# main.net
KiCad netlist of a schematic drawn in Altium Designer
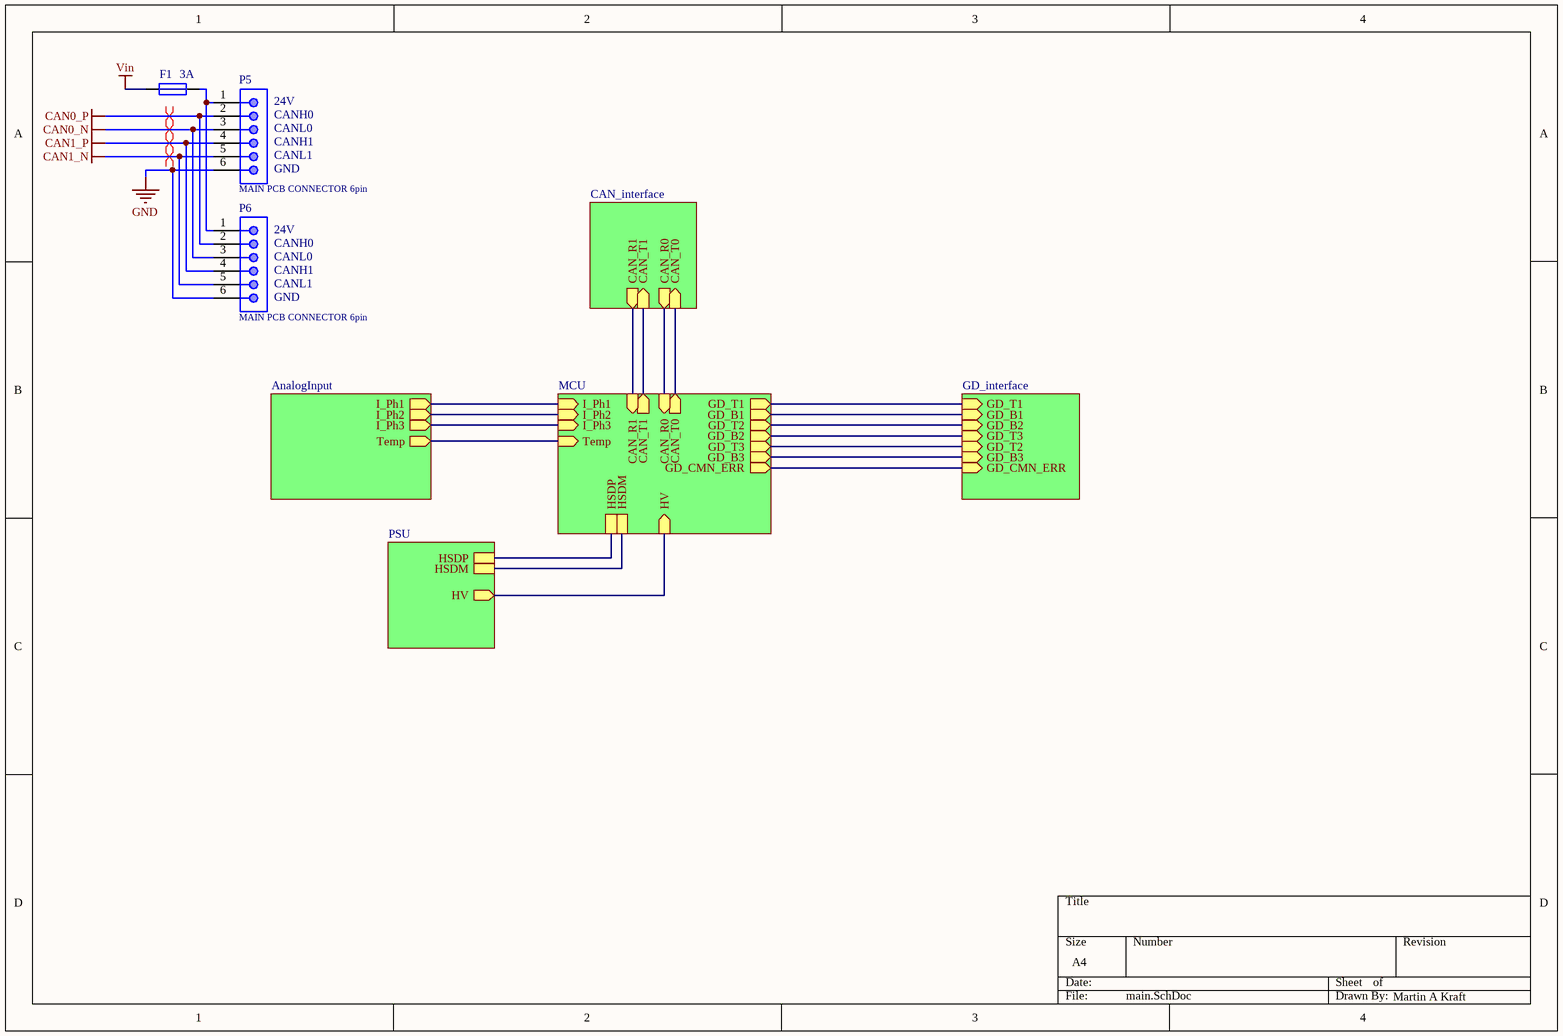
[diagram p0: main.SchDoc]

(export (version "E")
  (design (tool "Eeschema 10.0.6"))
  (components
    (comp (ref "F1")
      (value "3A")
      (footprint "F_OMH125")
      (description "Fuse - universal")
      (libsource (lib "M_Standard") (part "F_Fuse"))
    )
    (comp (ref "P5")
      (value "MAIN PCB CONNECTOR 6pin")
      (footprint "662106145021")
      (description "SMT Male Header WR-MPC3, with SMT Solder Tabs, Right Angled, Single Row, pitch 3 mm, 6 pins")
      (fields (field (name "PART NUMBER") "662106145021") (field (name "PUBLISHER") "Wurth Elektronik"))
      (libsource (lib "Wurth_connectors") (part "MAIN PCB CONNECTOR 6pin"))
    )
    (comp (ref "P6")
      (value "MAIN PCB CONNECTOR 6pin")
      (footprint "662106145021")
      (description "SMT Male Header WR-MPC3, with SMT Solder Tabs, Right Angled, Single Row, pitch 3 mm, 6 pins")
      (fields (field (name "PART NUMBER") "662106145021") (field (name "PUBLISHER") "Wurth Elektronik"))
      (libsource (lib "Wurth_connectors") (part "MAIN PCB CONNECTOR 6pin"))
    )
  )
  (nets
    (net (code "19") (name "CAN0_N") (class "Default")
      (node (ref "P5") (pin "3") (pintype "passive"))
      (node (ref "P6") (pin "3") (pintype "passive"))
    )
    (net (code "20") (name "CAN0_P") (class "Default")
      (node (ref "P5") (pin "2") (pintype "passive"))
      (node (ref "P6") (pin "2") (pintype "passive"))
    )
    (net (code "21") (name "CAN1_N") (class "Default")
      (node (ref "P5") (pin "5") (pintype "passive"))
      (node (ref "P6") (pin "5") (pintype "passive"))
    )
    (net (code "22") (name "CAN1_P") (class "Default")
      (node (ref "P5") (pin "4") (pintype "passive"))
      (node (ref "P6") (pin "4") (pintype "passive"))
    )
    (net (code "23") (name "GND") (class "Default")
      (node (ref "P5") (pin "6") (pintype "passive"))
      (node (ref "P6") (pin "6") (pintype "passive"))
    )
    (net (code "24") (name "Net-(F1-Pad2)") (class "Default")
      (node (ref "F1") (pin "2") (pinfunction "2_2") (pintype "passive"))
      (node (ref "P5") (pin "1") (pintype "passive"))
      (node (ref "P6") (pin "1") (pintype "passive"))
    )
    (net (code "25") (name "Vin") (class "Default")
      (node (ref "F1") (pin "1") (pinfunction "1_1") (pintype "passive"))
    )
  )
)
